# Power-LDO-Regulator_with_TL431_and_P-Mos.net
KiCad netlist of a schematic drawn in EAGLE
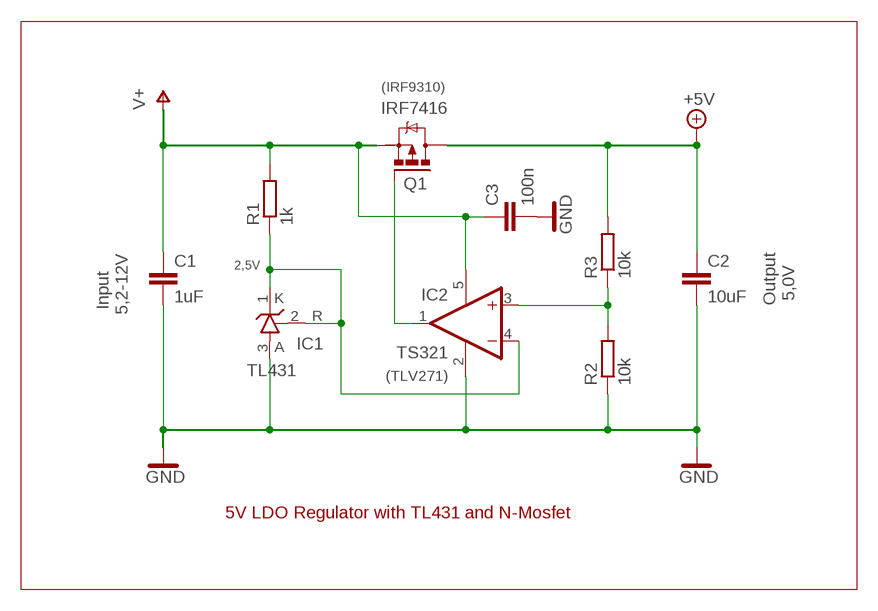
[diagram p0: schematic, sheet 1]

(export (version "E")
  (design (tool "Eeschema 10.0.6"))
  (components
    (comp (ref "C1")
      (value "1uF")
      (footprint "eagle-import:C0805")
      (libsource (lib "eagle-import") (part "C-EUC0805"))
    )
    (comp (ref "C2")
      (value "10uF")
      (footprint "eagle-import:C0805")
      (libsource (lib "eagle-import") (part "C-EUC0805"))
    )
    (comp (ref "C3")
      (value "100n")
      (footprint "eagle-import:C0603")
      (libsource (lib "eagle-import") (part "C-EUC0603"))
    )
    (comp (ref "IC1")
      (value "TL431")
      (footprint "eagle-import:SOT23")
      (libsource (lib "eagle-import") (part "TL431-SO23"))
    )
    (comp (ref "IC2")
      (value "TS321")
      (footprint "eagle-import:SOT23-5")
      (libsource (lib "eagle-import") (part "TS321SOT23-5"))
    )
    (comp (ref "Q1")
      (value "IRF7416")
      (footprint "eagle-import:SO-08")
      (libsource (lib "eagle-import") (part "P-MOSFET-SO8"))
    )
    (comp (ref "R1")
      (value "1k")
      (footprint "eagle-import:R0603")
      (libsource (lib "eagle-import") (part "R-EU_R0603"))
    )
    (comp (ref "R2")
      (value "10k")
      (footprint "eagle-import:R0603")
      (libsource (lib "eagle-import") (part "R-EU_R0603"))
    )
    (comp (ref "R3")
      (value "10k")
      (footprint "eagle-import:R0603")
      (libsource (lib "eagle-import") (part "R-EU_R0603"))
    )
  )
  (nets
    (net (code "1") (name "+5V") (class "Default")
      (node (ref "C2") (pin "1") (pinfunction "1_1") (pintype "passive"))
      (node (ref "Q1") (pin "5") (pinfunction "D_5") (pintype "passive"))
      (node (ref "Q1") (pin "6") (pinfunction "D_6") (pintype "passive"))
      (node (ref "Q1") (pin "7") (pinfunction "D_7") (pintype "passive"))
      (node (ref "Q1") (pin "8") (pinfunction "D_8") (pintype "passive"))
      (node (ref "R3") (pin "2") (pinfunction "2_2") (pintype "passive"))
    )
    (net (code "2") (name "GND") (class "Default")
      (node (ref "C1") (pin "2") (pinfunction "2_2") (pintype "passive"))
      (node (ref "C2") (pin "2") (pinfunction "2_2") (pintype "passive"))
      (node (ref "C3") (pin "2") (pinfunction "2_2") (pintype "passive"))
      (node (ref "IC1") (pin "3") (pinfunction "A_3") (pintype "passive"))
      (node (ref "IC2") (pin "2") (pinfunction "GND_2") (pintype "power_in"))
      (node (ref "R2") (pin "1") (pinfunction "1_1") (pintype "passive"))
    )
    (net (code "3") (name "Net-(IC1-C)") (class "Default")
      (node (ref "IC1") (pin "1") (pinfunction "C_1") (pintype "passive"))
      (node (ref "IC1") (pin "2") (pinfunction "R_2") (pintype "passive"))
      (node (ref "IC2") (pin "4") (pinfunction "-IN_4") (pintype "input"))
      (node (ref "R1") (pin "1") (pinfunction "1_1") (pintype "passive"))
    )
    (net (code "4") (name "Net-(IC2-+IN)") (class "Default")
      (node (ref "IC2") (pin "3") (pinfunction "+IN_3") (pintype "input"))
      (node (ref "R2") (pin "2") (pinfunction "2_2") (pintype "passive"))
      (node (ref "R3") (pin "1") (pinfunction "1_1") (pintype "passive"))
    )
    (net (code "5") (name "Net-(IC2-OUT)") (class "Default")
      (node (ref "IC2") (pin "1") (pinfunction "OUT_1") (pintype "output"))
      (node (ref "Q1") (pin "4") (pinfunction "G_4") (pintype "passive"))
    )
    (net (code "6") (name "V+") (class "Default")
      (node (ref "C1") (pin "1") (pinfunction "1_1") (pintype "passive"))
      (node (ref "C3") (pin "1") (pinfunction "1_1") (pintype "passive"))
      (node (ref "IC2") (pin "5") (pinfunction "V+_5") (pintype "power_in"))
      (node (ref "Q1") (pin "1") (pinfunction "S_1") (pintype "passive"))
      (node (ref "Q1") (pin "2") (pinfunction "S_2") (pintype "passive"))
      (node (ref "Q1") (pin "3") (pinfunction "S_3") (pintype "passive"))
      (node (ref "R1") (pin "2") (pinfunction "2_2") (pintype "passive"))
    )
  )
)
